# rc28c16rom.net
KiCad netlist of a schematic drawn in EAGLE
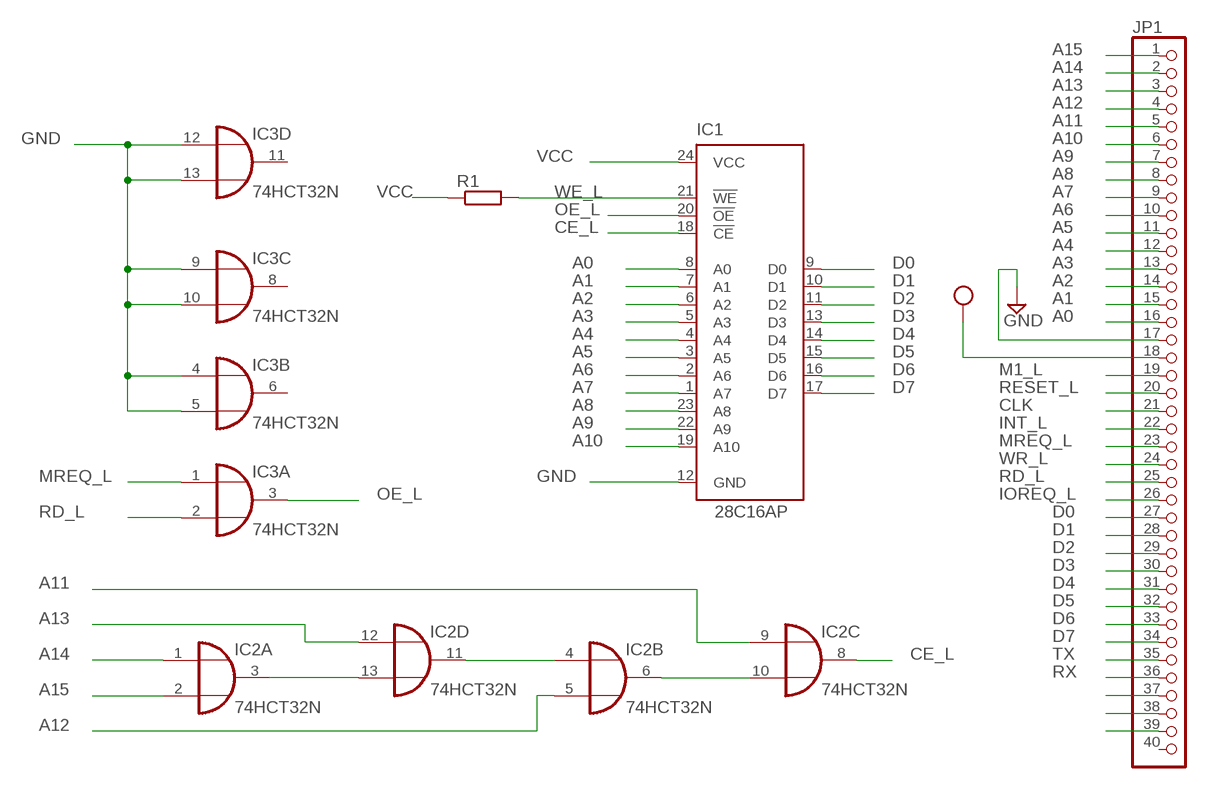
[diagram p0: schematic, sheet 1]

(export (version "E")
  (design (tool "Eeschema 10.0.6"))
  (components
    (comp (ref "IC1")
      (value "28C16AP")
      (footprint "eagle-import:DIL24-6")
      (fields (field (name "MPN") "CAT28C16ALI-12"))
      (libsource (lib "eagle-import") (part "2816APC"))
    )
    (comp (ref "IC2")
      (value "74HCT32N")
      (footprint "eagle-import:DIL14")
      (libsource (lib "eagle-import") (part "7432NHCT"))
    )
    (comp (ref "IC3")
      (value "74HCT32N")
      (footprint "eagle-import:DIL14")
      (libsource (lib "eagle-import") (part "7432NHCT"))
    )
    (comp (ref "JP1")
      (value "PINHD-1X40")
      (footprint "eagle-import:1X40")
      (libsource (lib "eagle-import") (part "PINHD-1X40"))
    )
    (comp (ref "R1")
      (value "R-EU_0204/5")
      (footprint "eagle-import:0204_5")
      (libsource (lib "eagle-import") (part "R-EU_0204/5"))
    )
  )
  (nets
    (net (code "1") (name "/A0") (class "Default")
      (node (ref "IC1") (pin "8") (pinfunction "A0_8") (pintype "input"))
      (node (ref "JP1") (pin "16") (pinfunction "16_16") (pintype "passive"))
    )
    (net (code "2") (name "/A1") (class "Default")
      (node (ref "IC1") (pin "7") (pinfunction "A1_7") (pintype "input"))
      (node (ref "JP1") (pin "15") (pinfunction "15_15") (pintype "passive"))
    )
    (net (code "3") (name "/A2") (class "Default")
      (node (ref "IC1") (pin "6") (pinfunction "A2_6") (pintype "input"))
      (node (ref "JP1") (pin "14") (pinfunction "14_14") (pintype "passive"))
    )
    (net (code "4") (name "/A3") (class "Default")
      (node (ref "IC1") (pin "5") (pinfunction "A3_5") (pintype "input"))
      (node (ref "JP1") (pin "13") (pinfunction "13_13") (pintype "passive"))
    )
    (net (code "5") (name "/A4") (class "Default")
      (node (ref "IC1") (pin "4") (pinfunction "A4_4") (pintype "input"))
      (node (ref "JP1") (pin "12") (pinfunction "12_12") (pintype "passive"))
    )
    (net (code "6") (name "/A5") (class "Default")
      (node (ref "IC1") (pin "3") (pinfunction "A5_3") (pintype "input"))
      (node (ref "JP1") (pin "11") (pinfunction "11_11") (pintype "passive"))
    )
    (net (code "7") (name "/A6") (class "Default")
      (node (ref "IC1") (pin "2") (pinfunction "A6_2") (pintype "input"))
      (node (ref "JP1") (pin "10") (pinfunction "10_10") (pintype "passive"))
    )
    (net (code "8") (name "/A7") (class "Default")
      (node (ref "IC1") (pin "1") (pinfunction "A7_1") (pintype "input"))
      (node (ref "JP1") (pin "9") (pinfunction "9_9") (pintype "passive"))
    )
    (net (code "9") (name "/A8") (class "Default")
      (node (ref "IC1") (pin "23") (pinfunction "A8_23") (pintype "input"))
      (node (ref "JP1") (pin "8") (pinfunction "8_8") (pintype "passive"))
    )
    (net (code "10") (name "/A9") (class "Default")
      (node (ref "IC1") (pin "22") (pinfunction "A9_22") (pintype "input"))
      (node (ref "JP1") (pin "7") (pinfunction "7_7") (pintype "passive"))
    )
    (net (code "11") (name "/A10") (class "Default")
      (node (ref "IC1") (pin "19") (pinfunction "A10_19") (pintype "input"))
      (node (ref "JP1") (pin "6") (pinfunction "6_6") (pintype "passive"))
    )
    (net (code "12") (name "/A11") (class "Default")
      (node (ref "IC2") (pin "9") (pinfunction "I0_9") (pintype "input"))
      (node (ref "JP1") (pin "5") (pinfunction "5_5") (pintype "passive"))
    )
    (net (code "13") (name "/A12") (class "Default")
      (node (ref "IC2") (pin "5") (pinfunction "I1_5") (pintype "input"))
      (node (ref "JP1") (pin "4") (pinfunction "4_4") (pintype "passive"))
    )
    (net (code "14") (name "/A13") (class "Default")
      (node (ref "IC2") (pin "12") (pinfunction "I0_12") (pintype "input"))
      (node (ref "JP1") (pin "3") (pinfunction "3_3") (pintype "passive"))
    )
    (net (code "15") (name "/A14") (class "Default")
      (node (ref "IC2") (pin "1") (pinfunction "I0_1") (pintype "input"))
      (node (ref "JP1") (pin "2") (pinfunction "2_2") (pintype "passive"))
    )
    (net (code "16") (name "/A15") (class "Default")
      (node (ref "IC2") (pin "2") (pinfunction "I1_2") (pintype "input"))
      (node (ref "JP1") (pin "1") (pinfunction "1_1") (pintype "passive"))
    )
    (net (code "17") (name "/CE_L") (class "Default")
      (node (ref "IC1") (pin "18") (pinfunction "~{CE}_18") (pintype "input"))
      (node (ref "IC2") (pin "8") (pinfunction "O_8") (pintype "output"))
    )
    (net (code "18") (name "/CLK") (class "Default")
      (node (ref "JP1") (pin "21") (pinfunction "21_21") (pintype "passive"))
    )
    (net (code "19") (name "/D0") (class "Default")
      (node (ref "IC1") (pin "9") (pinfunction "D0_9") (pintype "tri_state"))
      (node (ref "JP1") (pin "27") (pinfunction "27_27") (pintype "passive"))
    )
    (net (code "20") (name "/D1") (class "Default")
      (node (ref "IC1") (pin "10") (pinfunction "D1_10") (pintype "tri_state"))
      (node (ref "JP1") (pin "28") (pinfunction "28_28") (pintype "passive"))
    )
    (net (code "21") (name "/D2") (class "Default")
      (node (ref "IC1") (pin "11") (pinfunction "D2_11") (pintype "tri_state"))
      (node (ref "JP1") (pin "29") (pinfunction "29_29") (pintype "passive"))
    )
    (net (code "22") (name "/D3") (class "Default")
      (node (ref "IC1") (pin "13") (pinfunction "D3_13") (pintype "tri_state"))
      (node (ref "JP1") (pin "30") (pinfunction "30_30") (pintype "passive"))
    )
    (net (code "23") (name "/D4") (class "Default")
      (node (ref "IC1") (pin "14") (pinfunction "D4_14") (pintype "tri_state"))
      (node (ref "JP1") (pin "31") (pinfunction "31_31") (pintype "passive"))
    )
    (net (code "24") (name "/D5") (class "Default")
      (node (ref "IC1") (pin "15") (pinfunction "D5_15") (pintype "tri_state"))
      (node (ref "JP1") (pin "32") (pinfunction "32_32") (pintype "passive"))
    )
    (net (code "25") (name "/D6") (class "Default")
      (node (ref "IC1") (pin "16") (pinfunction "D6_16") (pintype "tri_state"))
      (node (ref "JP1") (pin "33") (pinfunction "33_33") (pintype "passive"))
    )
    (net (code "26") (name "/D7") (class "Default")
      (node (ref "IC1") (pin "17") (pinfunction "D7_17") (pintype "tri_state"))
      (node (ref "JP1") (pin "34") (pinfunction "34_34") (pintype "passive"))
    )
    (net (code "27") (name "/INT_L") (class "Default")
      (node (ref "JP1") (pin "22") (pinfunction "22_22") (pintype "passive"))
    )
    (net (code "28") (name "/IOREQ_L") (class "Default")
      (node (ref "JP1") (pin "26") (pinfunction "26_26") (pintype "passive"))
    )
    (net (code "29") (name "/M1_L") (class "Default")
      (node (ref "JP1") (pin "19") (pinfunction "19_19") (pintype "passive"))
    )
    (net (code "30") (name "/MREQ_L") (class "Default")
      (node (ref "IC3") (pin "1") (pinfunction "I0_1") (pintype "input"))
      (node (ref "JP1") (pin "23") (pinfunction "23_23") (pintype "passive"))
    )
    (net (code "31") (name "/OE_L") (class "Default")
      (node (ref "IC1") (pin "20") (pinfunction "~{OE}_20") (pintype "input"))
      (node (ref "IC3") (pin "3") (pinfunction "O_3") (pintype "output"))
    )
    (net (code "32") (name "/RD_L") (class "Default")
      (node (ref "IC3") (pin "2") (pinfunction "I1_2") (pintype "input"))
      (node (ref "JP1") (pin "25") (pinfunction "25_25") (pintype "passive"))
    )
    (net (code "33") (name "/RESET_L") (class "Default")
      (node (ref "JP1") (pin "20") (pinfunction "20_20") (pintype "passive"))
    )
    (net (code "34") (name "/RX") (class "Default")
      (node (ref "JP1") (pin "36") (pinfunction "36_36") (pintype "passive"))
    )
    (net (code "35") (name "/TX") (class "Default")
      (node (ref "JP1") (pin "35") (pinfunction "35_35") (pintype "passive"))
    )
    (net (code "36") (name "/WE_L") (class "Default")
      (node (ref "IC1") (pin "21") (pinfunction "~{WE}_21") (pintype "input"))
      (node (ref "R1") (pin "2") (pinfunction "2_2") (pintype "passive"))
    )
    (net (code "37") (name "/WR_L") (class "Default")
      (node (ref "JP1") (pin "24") (pinfunction "24_24") (pintype "passive"))
    )
    (net (code "38") (name "GND") (class "Default")
      (node (ref "IC1") (pin "12") (pinfunction "GND_12") (pintype "power_in"))
      (node (ref "IC3") (pin "10") (pinfunction "I1_10") (pintype "input"))
      (node (ref "IC3") (pin "12") (pinfunction "I0_12") (pintype "input"))
      (node (ref "IC3") (pin "13") (pinfunction "I1_13") (pintype "input"))
      (node (ref "IC3") (pin "4") (pinfunction "I0_4") (pintype "input"))
      (node (ref "IC3") (pin "5") (pinfunction "I1_5") (pintype "input"))
      (node (ref "IC3") (pin "9") (pinfunction "I0_9") (pintype "input"))
      (node (ref "JP1") (pin "17") (pinfunction "17_17") (pintype "passive"))
    )
    (net (code "39") (name "Net-(IC2A-O)") (class "Default")
      (node (ref "IC2") (pin "13") (pinfunction "I1_13") (pintype "input"))
      (node (ref "IC2") (pin "3") (pinfunction "O_3") (pintype "output"))
    )
    (net (code "40") (name "Net-(IC2B-I0)") (class "Default")
      (node (ref "IC2") (pin "11") (pinfunction "O_11") (pintype "output"))
      (node (ref "IC2") (pin "4") (pinfunction "I0_4") (pintype "input"))
    )
    (net (code "41") (name "Net-(IC2B-O)") (class "Default")
      (node (ref "IC2") (pin "10") (pinfunction "I1_10") (pintype "input"))
      (node (ref "IC2") (pin "6") (pinfunction "O_6") (pintype "output"))
    )
    (net (code "42") (name "VCC") (class "Default")
      (node (ref "IC1") (pin "24") (pinfunction "VCC_24") (pintype "power_in"))
      (node (ref "JP1") (pin "18") (pinfunction "18_18") (pintype "passive"))
      (node (ref "R1") (pin "1") (pinfunction "1_1") (pintype "passive"))
    )
    (net (code "43") (name "unconnected-(IC3B-O-Pad6)") (class "Default")
      (node (ref "IC3") (pin "6") (pinfunction "O_6") (pintype "output"))
    )
    (net (code "44") (name "unconnected-(IC3C-O-Pad8)") (class "Default")
      (node (ref "IC3") (pin "8") (pinfunction "O_8") (pintype "output"))
    )
    (net (code "45") (name "unconnected-(IC3D-O-Pad11)") (class "Default")
      (node (ref "IC3") (pin "11") (pinfunction "O_11") (pintype "output"))
    )
    (net (code "46") (name "unconnected-(JP1-Pad37)") (class "Default")
      (node (ref "JP1") (pin "37") (pinfunction "37_37") (pintype "passive"))
    )
    (net (code "47") (name "unconnected-(JP1-Pad38)") (class "Default")
      (node (ref "JP1") (pin "38") (pinfunction "38_38") (pintype "passive"))
    )
    (net (code "48") (name "unconnected-(JP1-Pad39)") (class "Default")
      (node (ref "JP1") (pin "39") (pinfunction "39_39") (pintype "passive"))
    )
    (net (code "49") (name "unconnected-(JP1-Pad40)") (class "Default")
      (node (ref "JP1") (pin "40") (pinfunction "40_40") (pintype "passive"))
    )
  )
)
